# BATTERY_BOARD.net
KiCad netlist of a schematic drawn in Altium Designer
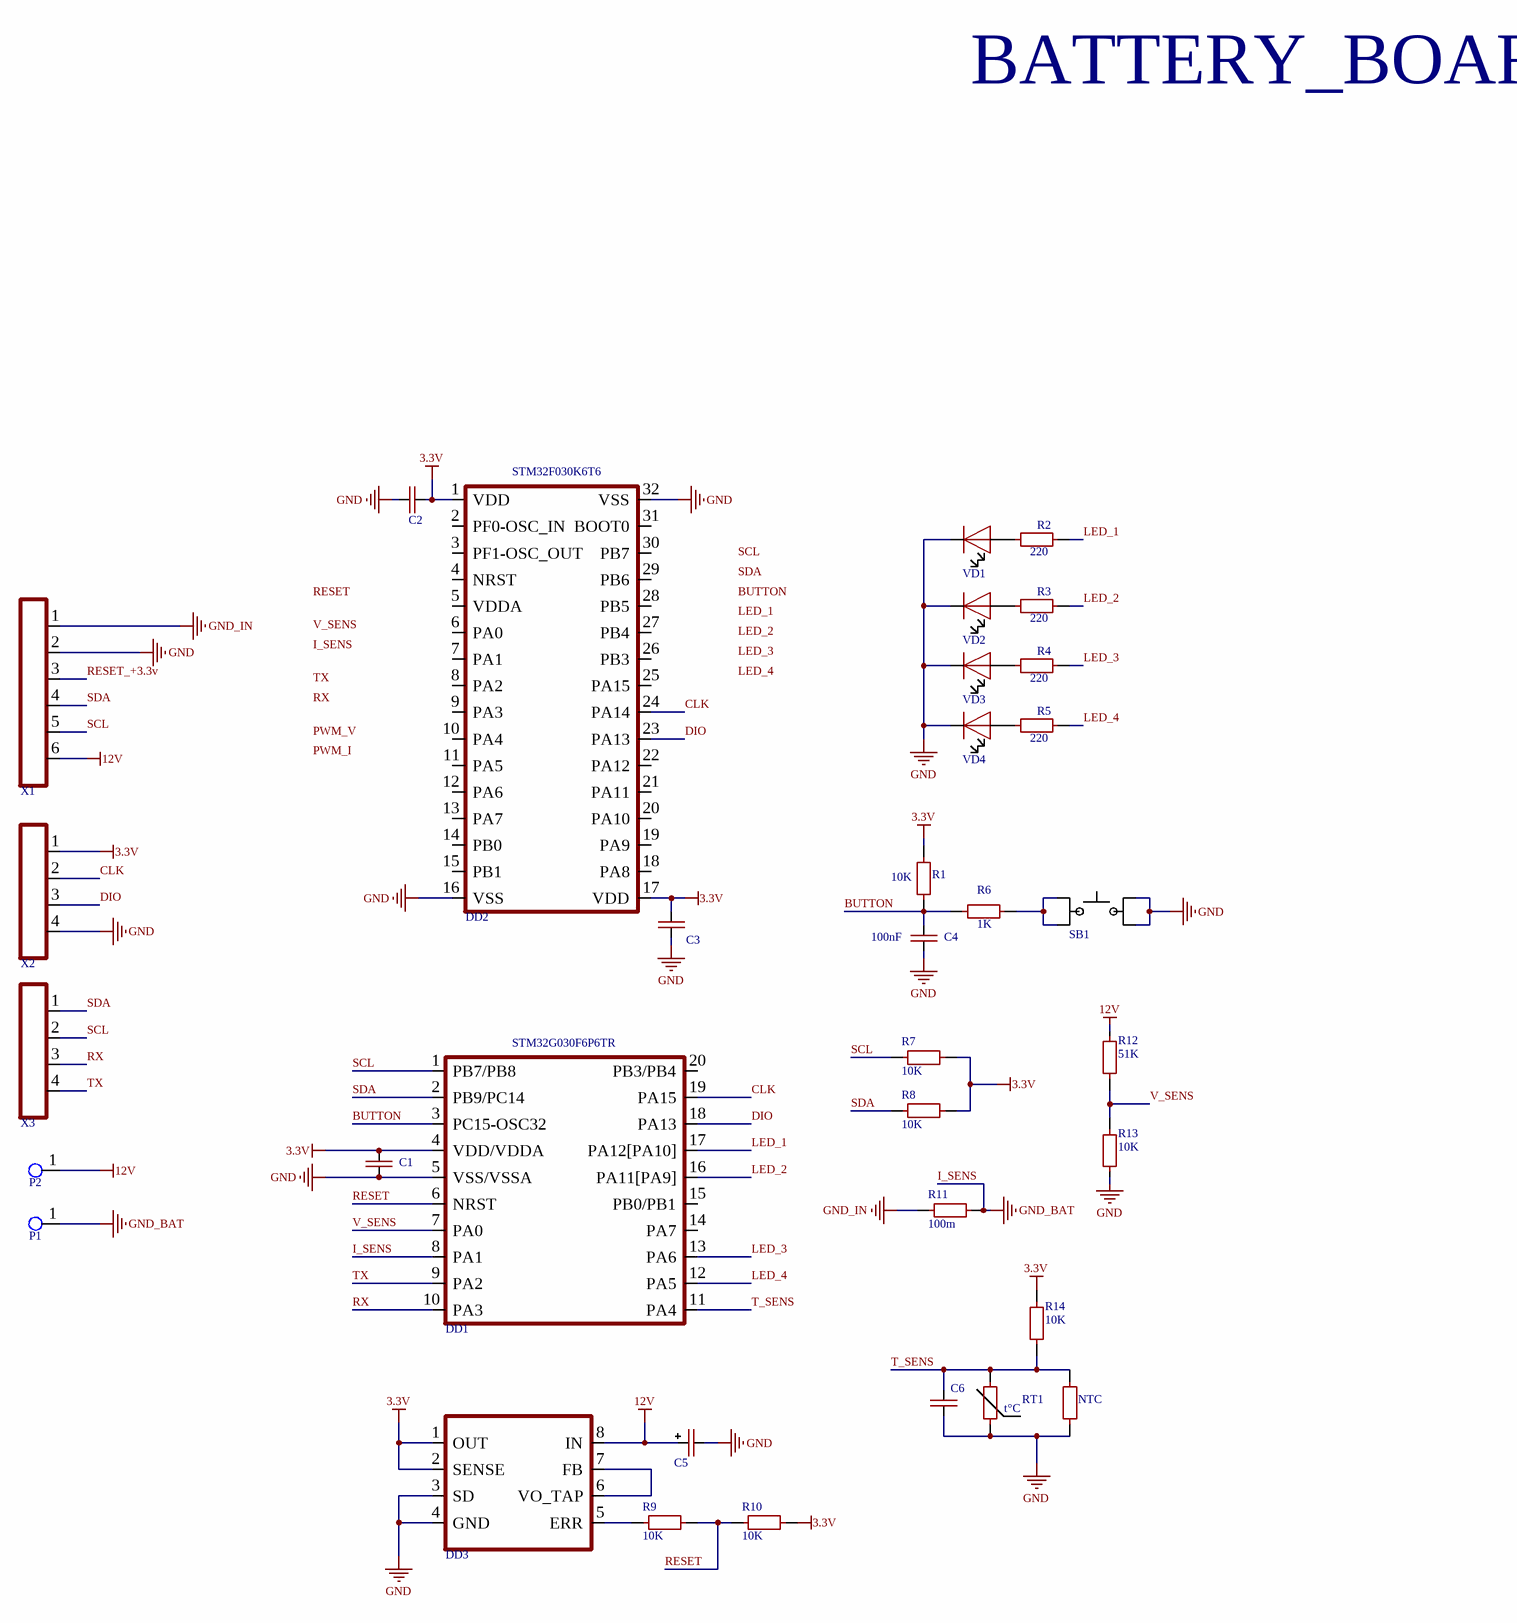
[diagram p0: BATTERY_BOARD.SchDoc]

(export (version "E")
  (design (tool "Eeschema 10.0.6"))
  (components
    (comp (ref "C1")
      (value "CAP-NON-POLAR")
      (footprint "CAP-0603")
      (libsource (lib "PASSIVE_COMPONENTS") (part "CAP-NON-POLAR"))
    )
    (comp (ref "C2")
      (value "CAP-NON-POLAR")
      (footprint "CAP-0603")
      (libsource (lib "PASSIVE_COMPONENTS") (part "CAP-NON-POLAR"))
    )
    (comp (ref "C3")
      (value "CAP-NON-POLAR")
      (footprint "CAP-0603")
      (libsource (lib "PASSIVE_COMPONENTS") (part "CAP-NON-POLAR"))
    )
    (comp (ref "C4")
      (value "100nF")
      (footprint "CAP-0603")
      (libsource (lib "PASSIVE_COMPONENTS") (part "CAP-NON-POLAR"))
    )
    (comp (ref "C5")
      (value "CAP-POLAR")
      (footprint "CAP-TAN-C")
      (libsource (lib "PASSIVE_COMPONENTS") (part "CAP-POLAR"))
    )
    (comp (ref "C6")
      (value "CAP-NON-POLAR")
      (footprint "CAP-0805")
      (libsource (lib "PASSIVE_COMPONENTS") (part "CAP-NON-POLAR"))
    )
    (comp (ref "DD1")
      (value "STM32G030F6P6TR")
      (footprint "TSSOP-20")
      (libsource (lib "STM32G030F6P6TR") (part "STM32G030F6P6TR"))
    )
    (comp (ref "DD2")
      (value "STM32F030K6T6")
      (footprint "LQFP32")
      (libsource (lib "STM32F030K6T6") (part "STM32F030K6T6"))
    )
    (comp (ref "DD3") (value "LP2951") (footprint "SO8-150") (libsource (lib "LP2951") (part "LP2951")))
    (comp (ref "NTC")
      (value "RES-CONST")
      (footprint "RES-0805")
      (libsource (lib "PASSIVE_COMPONENTS") (part "RES-CONST"))
    )
    (comp (ref "P1") (value "Test_Point_PCB") (footprint "Point") (libsource (lib "POINT") (part "POINT")))
    (comp (ref "P2") (value "Test_Point_PCB") (footprint "Point") (libsource (lib "POINT") (part "POINT")))
    (comp (ref "R1")
      (value "10K")
      (footprint "RES-0603")
      (libsource (lib "PASSIVE_COMPONENTS") (part "RES-CONST"))
    )
    (comp (ref "R2")
      (value "220")
      (footprint "RES-0603")
      (libsource (lib "PASSIVE_COMPONENTS") (part "RES-CONST"))
    )
    (comp (ref "R3")
      (value "220")
      (footprint "RES-0603")
      (libsource (lib "PASSIVE_COMPONENTS") (part "RES-CONST"))
    )
    (comp (ref "R4")
      (value "220")
      (footprint "RES-0603")
      (libsource (lib "PASSIVE_COMPONENTS") (part "RES-CONST"))
    )
    (comp (ref "R5")
      (value "220")
      (footprint "RES-0603")
      (libsource (lib "PASSIVE_COMPONENTS") (part "RES-CONST"))
    )
    (comp (ref "R6")
      (value "1K")
      (footprint "RES-0603")
      (libsource (lib "PASSIVE_COMPONENTS") (part "RES-CONST"))
    )
    (comp (ref "R7")
      (value "10K")
      (footprint "RES-0603")
      (libsource (lib "PASSIVE_COMPONENTS") (part "RES-CONST"))
    )
    (comp (ref "R8")
      (value "10K")
      (footprint "RES-0603")
      (libsource (lib "PASSIVE_COMPONENTS") (part "RES-CONST"))
    )
    (comp (ref "R9")
      (value "10K")
      (footprint "RES-0603")
      (libsource (lib "PASSIVE_COMPONENTS") (part "RES-CONST"))
    )
    (comp (ref "R10")
      (value "10K")
      (footprint "RES-0603")
      (libsource (lib "PASSIVE_COMPONENTS") (part "RES-CONST"))
    )
    (comp (ref "R11")
      (value "100m")
      (footprint "RES-2512")
      (libsource (lib "PASSIVE_COMPONENTS") (part "RES-CONST"))
    )
    (comp (ref "R12")
      (value "51K")
      (footprint "RES-0603")
      (libsource (lib "PASSIVE_COMPONENTS") (part "RES-CONST"))
    )
    (comp (ref "R13")
      (value "10K")
      (footprint "RES-0603")
      (libsource (lib "PASSIVE_COMPONENTS") (part "RES-CONST"))
    )
    (comp (ref "R14")
      (value "10K")
      (footprint "RES-0603")
      (libsource (lib "PASSIVE_COMPONENTS") (part "RES-CONST"))
    )
    (comp (ref "RT1") (value "RES-TEMP") (footprint "NTC_MF52") (libsource (lib "NTC") (part "RES-TEMP")))
    (comp (ref "SB1")
      (value "BUTTON-TACT-4PIN")
      (footprint "TACTB-6x6 SMD")
      (libsource (lib "TACTB-6x6 SMD") (part "BUTTON-TACT-4PIN"))
    )
    (comp (ref "VD1") (value "LED") (footprint "LED-0603") (libsource (lib "LED") (part "LED")))
    (comp (ref "VD2") (value "LED") (footprint "LED-0603") (libsource (lib "LED") (part "LED")))
    (comp (ref "VD3") (value "LED") (footprint "LED-0603") (libsource (lib "LED") (part "LED")))
    (comp (ref "VD4") (value "LED") (footprint "LED-0603") (libsource (lib "LED") (part "LED")))
    (comp (ref "X1")
      (value "CONN-6-PIN")
      (footprint "CON_6PIN_BATT_DEFIBRILLATOR")
      (libsource (lib "CON_6PIN_BATT_DEFIBRILLATOR") (part "CONN-6-PIN"))
    )
    (comp (ref "X2")
      (value "CONN-4-PIN")
      (footprint "CONN-PLS-4-2.54mm")
      (libsource (lib "CONNECTORS") (part "CONN-4-PIN"))
    )
    (comp (ref "X3")
      (value "CONN-4-PIN")
      (footprint "CONN-PLS-4-2.54mm")
      (libsource (lib "CONNECTORS") (part "CONN-4-PIN"))
    )
  )
  (nets
    (net (code "1") (name "/BUTTON") (class "Default")
      (node (ref "C4") (pin "2") (pinfunction "2_2") (pintype "passive"))
      (node (ref "DD1") (pin "3") (pinfunction "PC15-OSC32_3") (pintype "passive"))
      (node (ref "R1") (pin "1") (pinfunction "1_1") (pintype "passive"))
      (node (ref "R6") (pin "1") (pinfunction "1_1") (pintype "passive"))
    )
    (net (code "2") (name "/CLK") (class "Default")
      (node (ref "DD1") (pin "19") (pinfunction "PA15_19") (pintype "passive"))
      (node (ref "DD2") (pin "24") (pinfunction "PA14_24") (pintype "passive"))
      (node (ref "X2") (pin "2") (pinfunction "2_2") (pintype "passive"))
    )
    (net (code "3") (name "/DIO") (class "Default")
      (node (ref "DD1") (pin "18") (pinfunction "PA13_18") (pintype "passive"))
      (node (ref "DD2") (pin "23") (pinfunction "PA13_23") (pintype "passive"))
      (node (ref "X2") (pin "3") (pinfunction "3_3") (pintype "passive"))
    )
    (net (code "4") (name "/LED_1") (class "Default")
      (node (ref "DD1") (pin "17") (pinfunction "PA12[PA10]_17") (pintype "passive"))
      (node (ref "R2") (pin "2") (pinfunction "2_2") (pintype "passive"))
    )
    (net (code "5") (name "/LED_2") (class "Default")
      (node (ref "DD1") (pin "16") (pinfunction "PA11[PA9]_16") (pintype "passive"))
      (node (ref "R3") (pin "2") (pinfunction "2_2") (pintype "passive"))
    )
    (net (code "6") (name "/LED_3") (class "Default")
      (node (ref "DD1") (pin "13") (pinfunction "PA6_13") (pintype "passive"))
      (node (ref "R4") (pin "2") (pinfunction "2_2") (pintype "passive"))
    )
    (net (code "7") (name "/LED_4") (class "Default")
      (node (ref "DD1") (pin "12") (pinfunction "PA5_12") (pintype "passive"))
      (node (ref "R5") (pin "2") (pinfunction "2_2") (pintype "passive"))
    )
    (net (code "10") (name "/RESET") (class "Default")
      (node (ref "DD1") (pin "6") (pinfunction "NRST_6") (pintype "passive"))
      (node (ref "R10") (pin "2") (pinfunction "2_2") (pintype "passive"))
      (node (ref "R9") (pin "1") (pinfunction "1_1") (pintype "passive"))
    )
    (net (code "11") (name "/RESET_+3.3v") (class "Default")
      (node (ref "X1") (pin "3") (pinfunction "3_3") (pintype "passive"))
    )
    (net (code "12") (name "/RX") (class "Default")
      (node (ref "DD1") (pin "10") (pinfunction "PA3_10") (pintype "passive"))
      (node (ref "X3") (pin "3") (pinfunction "3_3") (pintype "passive"))
    )
    (net (code "13") (name "/SCL") (class "Default")
      (node (ref "DD1") (pin "1") (pinfunction "PB7/PB8_1") (pintype "passive"))
      (node (ref "R7") (pin "2") (pinfunction "2_2") (pintype "passive"))
      (node (ref "X1") (pin "5") (pinfunction "5_5") (pintype "passive"))
      (node (ref "X3") (pin "2") (pinfunction "2_2") (pintype "passive"))
    )
    (net (code "14") (name "/SDA") (class "Default")
      (node (ref "DD1") (pin "2") (pinfunction "PB9/PC14_2") (pintype "passive"))
      (node (ref "R8") (pin "2") (pinfunction "2_2") (pintype "passive"))
      (node (ref "X1") (pin "4") (pinfunction "4_4") (pintype "passive"))
      (node (ref "X3") (pin "1") (pinfunction "1_1") (pintype "passive"))
    )
    (net (code "15") (name "/TX") (class "Default")
      (node (ref "DD1") (pin "9") (pinfunction "PA2_9") (pintype "passive"))
      (node (ref "X3") (pin "4") (pinfunction "4_4") (pintype "passive"))
    )
    (net (code "16") (name "/T_SENS") (class "Default")
      (node (ref "C6") (pin "2") (pinfunction "2_2") (pintype "passive"))
      (node (ref "DD1") (pin "11") (pinfunction "PA4_11") (pintype "passive"))
      (node (ref "NTC") (pin "2") (pinfunction "2_2") (pintype "passive"))
      (node (ref "R14") (pin "2") (pinfunction "2_2") (pintype "passive"))
      (node (ref "RT1") (pin "2") (pinfunction "2_2") (pintype "passive"))
    )
    (net (code "17") (name "/V_SENS") (class "Default")
      (node (ref "DD1") (pin "7") (pinfunction "PA0_7") (pintype "passive"))
      (node (ref "R12") (pin "2") (pinfunction "2_2") (pintype "passive"))
      (node (ref "R13") (pin "1") (pinfunction "1_1") (pintype "passive"))
    )
    (net (code "18") (name "3.3V") (class "Default")
      (node (ref "C1") (pin "2") (pinfunction "2_2") (pintype "passive"))
      (node (ref "C2") (pin "2") (pinfunction "2_2") (pintype "passive"))
      (node (ref "C3") (pin "2") (pinfunction "2_2") (pintype "passive"))
      (node (ref "DD1") (pin "4") (pinfunction "VDD/VDDA_4") (pintype "passive"))
      (node (ref "DD2") (pin "1") (pinfunction "VDD_1") (pintype "passive"))
      (node (ref "DD2") (pin "17") (pinfunction "VDD_17") (pintype "passive"))
      (node (ref "DD3") (pin "1") (pinfunction "OUT_1") (pintype "passive"))
      (node (ref "DD3") (pin "2") (pinfunction "SENSE_2") (pintype "passive"))
      (node (ref "R1") (pin "2") (pinfunction "2_2") (pintype "passive"))
      (node (ref "R10") (pin "1") (pinfunction "1_1") (pintype "passive"))
      (node (ref "R14") (pin "1") (pinfunction "1_1") (pintype "passive"))
      (node (ref "R7") (pin "1") (pinfunction "1_1") (pintype "passive"))
      (node (ref "R8") (pin "1") (pinfunction "1_1") (pintype "passive"))
      (node (ref "X2") (pin "1") (pinfunction "1_1") (pintype "passive"))
    )
    (net (code "19") (name "12V") (class "Default")
      (node (ref "C5") (pin "1") (pinfunction "+_1") (pintype "passive"))
      (node (ref "DD3") (pin "8") (pinfunction "IN_8") (pintype "passive"))
      (node (ref "P2") (pin "1") (pinfunction "G9_1") (pintype "passive"))
      (node (ref "R12") (pin "1") (pinfunction "1_1") (pintype "passive"))
      (node (ref "X1") (pin "6") (pinfunction "6_6") (pintype "passive"))
    )
    (net (code "20") (name "GND") (class "Default")
      (node (ref "C1") (pin "1") (pinfunction "1_1") (pintype "passive"))
      (node (ref "C2") (pin "1") (pinfunction "1_1") (pintype "passive"))
      (node (ref "C3") (pin "1") (pinfunction "1_1") (pintype "passive"))
      (node (ref "C4") (pin "1") (pinfunction "1_1") (pintype "passive"))
      (node (ref "C5") (pin "2") (pinfunction "-_2") (pintype "passive"))
      (node (ref "C6") (pin "1") (pinfunction "1_1") (pintype "passive"))
      (node (ref "DD1") (pin "5") (pinfunction "VSS/VSSA_5") (pintype "passive"))
      (node (ref "DD2") (pin "16") (pinfunction "VSS_16") (pintype "passive"))
      (node (ref "DD2") (pin "32") (pinfunction "VSS_32") (pintype "passive"))
      (node (ref "DD3") (pin "3") (pinfunction "SD_3") (pintype "passive"))
      (node (ref "DD3") (pin "4") (pinfunction "GND_4") (pintype "passive"))
      (node (ref "NTC") (pin "1") (pinfunction "1_1") (pintype "passive"))
      (node (ref "R13") (pin "2") (pinfunction "2_2") (pintype "passive"))
      (node (ref "RT1") (pin "1") (pinfunction "1_1") (pintype "passive"))
      (node (ref "SB1") (pin "3") (pintype "passive"))
      (node (ref "SB1") (pin "4") (pintype "passive"))
      (node (ref "VD1") (pin "1") (pinfunction "C_1") (pintype "passive"))
      (node (ref "VD2") (pin "1") (pinfunction "C_1") (pintype "passive"))
      (node (ref "VD3") (pin "1") (pinfunction "C_1") (pintype "passive"))
      (node (ref "VD4") (pin "1") (pinfunction "C_1") (pintype "passive"))
      (node (ref "X1") (pin "2") (pinfunction "2_2") (pintype "passive"))
      (node (ref "X2") (pin "4") (pinfunction "4_4") (pintype "passive"))
    )
    (net (code "21") (name "GND_BAT") (class "Default")
      (node (ref "DD1") (pin "8") (pinfunction "PA1_8") (pintype "passive"))
      (node (ref "P1") (pin "1") (pinfunction "G9_1") (pintype "passive"))
      (node (ref "R11") (pin "2") (pinfunction "2_2") (pintype "passive"))
    )
    (net (code "22") (name "GND_IN") (class "Default")
      (node (ref "R11") (pin "1") (pinfunction "1_1") (pintype "passive"))
      (node (ref "X1") (pin "1") (pinfunction "1_1") (pintype "passive"))
    )
    (net (code "23") (name "Net-(DD3-ERR)") (class "Default")
      (node (ref "DD3") (pin "5") (pinfunction "ERR_5") (pintype "passive"))
      (node (ref "R9") (pin "2") (pinfunction "2_2") (pintype "passive"))
    )
    (net (code "24") (name "Net-(DD3-FB)") (class "Default")
      (node (ref "DD3") (pin "6") (pinfunction "VO_TAP_6") (pintype "passive"))
      (node (ref "DD3") (pin "7") (pinfunction "FB_7") (pintype "passive"))
    )
    (net (code "25") (name "Net-(R6-Pad2)") (class "Default")
      (node (ref "R6") (pin "2") (pinfunction "2_2") (pintype "passive"))
      (node (ref "SB1") (pin "1") (pintype "passive"))
      (node (ref "SB1") (pin "2") (pintype "passive"))
    )
    (net (code "26") (name "Net-(VD1-A)") (class "Default")
      (node (ref "R2") (pin "1") (pinfunction "1_1") (pintype "passive"))
      (node (ref "VD1") (pin "2") (pinfunction "A_2") (pintype "passive"))
    )
    (net (code "27") (name "Net-(VD2-A)") (class "Default")
      (node (ref "R3") (pin "1") (pinfunction "1_1") (pintype "passive"))
      (node (ref "VD2") (pin "2") (pinfunction "A_2") (pintype "passive"))
    )
    (net (code "28") (name "Net-(VD3-A)") (class "Default")
      (node (ref "R4") (pin "1") (pinfunction "1_1") (pintype "passive"))
      (node (ref "VD3") (pin "2") (pinfunction "A_2") (pintype "passive"))
    )
    (net (code "29") (name "Net-(VD4-A)") (class "Default")
      (node (ref "R5") (pin "1") (pinfunction "1_1") (pintype "passive"))
      (node (ref "VD4") (pin "2") (pinfunction "A_2") (pintype "passive"))
    )
    (net (code "30") (name "unconnected-(DD1-PA7-Pad14)") (class "Default")
      (node (ref "DD1") (pin "14") (pinfunction "PA7_14") (pintype "passive"))
    )
    (net (code "31") (name "unconnected-(DD1-PB0{slash}PB1-Pad15)") (class "Default")
      (node (ref "DD1") (pin "15") (pinfunction "PB0/PB1_15") (pintype "passive"))
    )
    (net (code "32") (name "unconnected-(DD1-PB3{slash}PB4-Pad20)") (class "Default")
      (node (ref "DD1") (pin "20") (pinfunction "PB3/PB4_20") (pintype "passive"))
    )
    (net (code "33") (name "unconnected-(DD2-BOOT0-Pad31)") (class "Default")
      (node (ref "DD2") (pin "31") (pinfunction "BOOT0_31") (pintype "passive"))
    )
    (net (code "34") (name "unconnected-(DD2-NRST-Pad4)") (class "Default")
      (node (ref "DD2") (pin "4") (pinfunction "NRST_4") (pintype "passive"))
    )
    (net (code "35") (name "unconnected-(DD2-PA0-Pad6)") (class "Default")
      (node (ref "DD2") (pin "6") (pinfunction "PA0_6") (pintype "passive"))
    )
    (net (code "36") (name "unconnected-(DD2-PA1-Pad7)") (class "Default")
      (node (ref "DD2") (pin "7") (pinfunction "PA1_7") (pintype "passive"))
    )
    (net (code "37") (name "unconnected-(DD2-PA2-Pad8)") (class "Default")
      (node (ref "DD2") (pin "8") (pinfunction "PA2_8") (pintype "passive"))
    )
    (net (code "38") (name "unconnected-(DD2-PA3-Pad9)") (class "Default")
      (node (ref "DD2") (pin "9") (pinfunction "PA3_9") (pintype "passive"))
    )
    (net (code "39") (name "unconnected-(DD2-PA4-Pad10)") (class "Default")
      (node (ref "DD2") (pin "10") (pinfunction "PA4_10") (pintype "passive"))
    )
    (net (code "40") (name "unconnected-(DD2-PA5-Pad11)") (class "Default")
      (node (ref "DD2") (pin "11") (pinfunction "PA5_11") (pintype "passive"))
    )
    (net (code "41") (name "unconnected-(DD2-PA6-Pad12)") (class "Default")
      (node (ref "DD2") (pin "12") (pinfunction "PA6_12") (pintype "passive"))
    )
    (net (code "42") (name "unconnected-(DD2-PA7-Pad13)") (class "Default")
      (node (ref "DD2") (pin "13") (pinfunction "PA7_13") (pintype "passive"))
    )
    (net (code "43") (name "unconnected-(DD2-PA8-Pad18)") (class "Default")
      (node (ref "DD2") (pin "18") (pinfunction "PA8_18") (pintype "passive"))
    )
    (net (code "44") (name "unconnected-(DD2-PA9-Pad19)") (class "Default")
      (node (ref "DD2") (pin "19") (pinfunction "PA9_19") (pintype "passive"))
    )
    (net (code "45") (name "unconnected-(DD2-PA10-Pad20)") (class "Default")
      (node (ref "DD2") (pin "20") (pinfunction "PA10_20") (pintype "passive"))
    )
    (net (code "46") (name "unconnected-(DD2-PA11-Pad21)") (class "Default")
      (node (ref "DD2") (pin "21") (pinfunction "PA11_21") (pintype "passive"))
    )
    (net (code "47") (name "unconnected-(DD2-PA12-Pad22)") (class "Default")
      (node (ref "DD2") (pin "22") (pinfunction "PA12_22") (pintype "passive"))
    )
    (net (code "48") (name "unconnected-(DD2-PA15-Pad25)") (class "Default")
      (node (ref "DD2") (pin "25") (pinfunction "PA15_25") (pintype "passive"))
    )
    (net (code "49") (name "unconnected-(DD2-PB0-Pad14)") (class "Default")
      (node (ref "DD2") (pin "14") (pinfunction "PB0_14") (pintype "passive"))
    )
    (net (code "50") (name "unconnected-(DD2-PB1-Pad15)") (class "Default")
      (node (ref "DD2") (pin "15") (pinfunction "PB1_15") (pintype "passive"))
    )
    (net (code "51") (name "unconnected-(DD2-PB3-Pad26)") (class "Default")
      (node (ref "DD2") (pin "26") (pinfunction "PB3_26") (pintype "passive"))
    )
    (net (code "52") (name "unconnected-(DD2-PB4-Pad27)") (class "Default")
      (node (ref "DD2") (pin "27") (pinfunction "PB4_27") (pintype "passive"))
    )
    (net (code "53") (name "unconnected-(DD2-PB5-Pad28)") (class "Default")
      (node (ref "DD2") (pin "28") (pinfunction "PB5_28") (pintype "passive"))
    )
    (net (code "54") (name "unconnected-(DD2-PB6-Pad29)") (class "Default")
      (node (ref "DD2") (pin "29") (pinfunction "PB6_29") (pintype "passive"))
    )
    (net (code "55") (name "unconnected-(DD2-PB7-Pad30)") (class "Default")
      (node (ref "DD2") (pin "30") (pinfunction "PB7_30") (pintype "passive"))
    )
    (net (code "56") (name "unconnected-(DD2-PF0-OSC_IN-Pad2)") (class "Default")
      (node (ref "DD2") (pin "2") (pinfunction "PF0-OSC_IN_2") (pintype "passive"))
    )
    (net (code "57") (name "unconnected-(DD2-PF1-OSC_OUT-Pad3)") (class "Default")
      (node (ref "DD2") (pin "3") (pinfunction "PF1-OSC_OUT_3") (pintype "passive"))
    )
    (net (code "58") (name "unconnected-(DD2-VDDA-Pad5)") (class "Default")
      (node (ref "DD2") (pin "5") (pinfunction "VDDA_5") (pintype "passive"))
    )
  )
)
